# 1.net
KiCad netlist of a schematic drawn in EasyEDA Pro
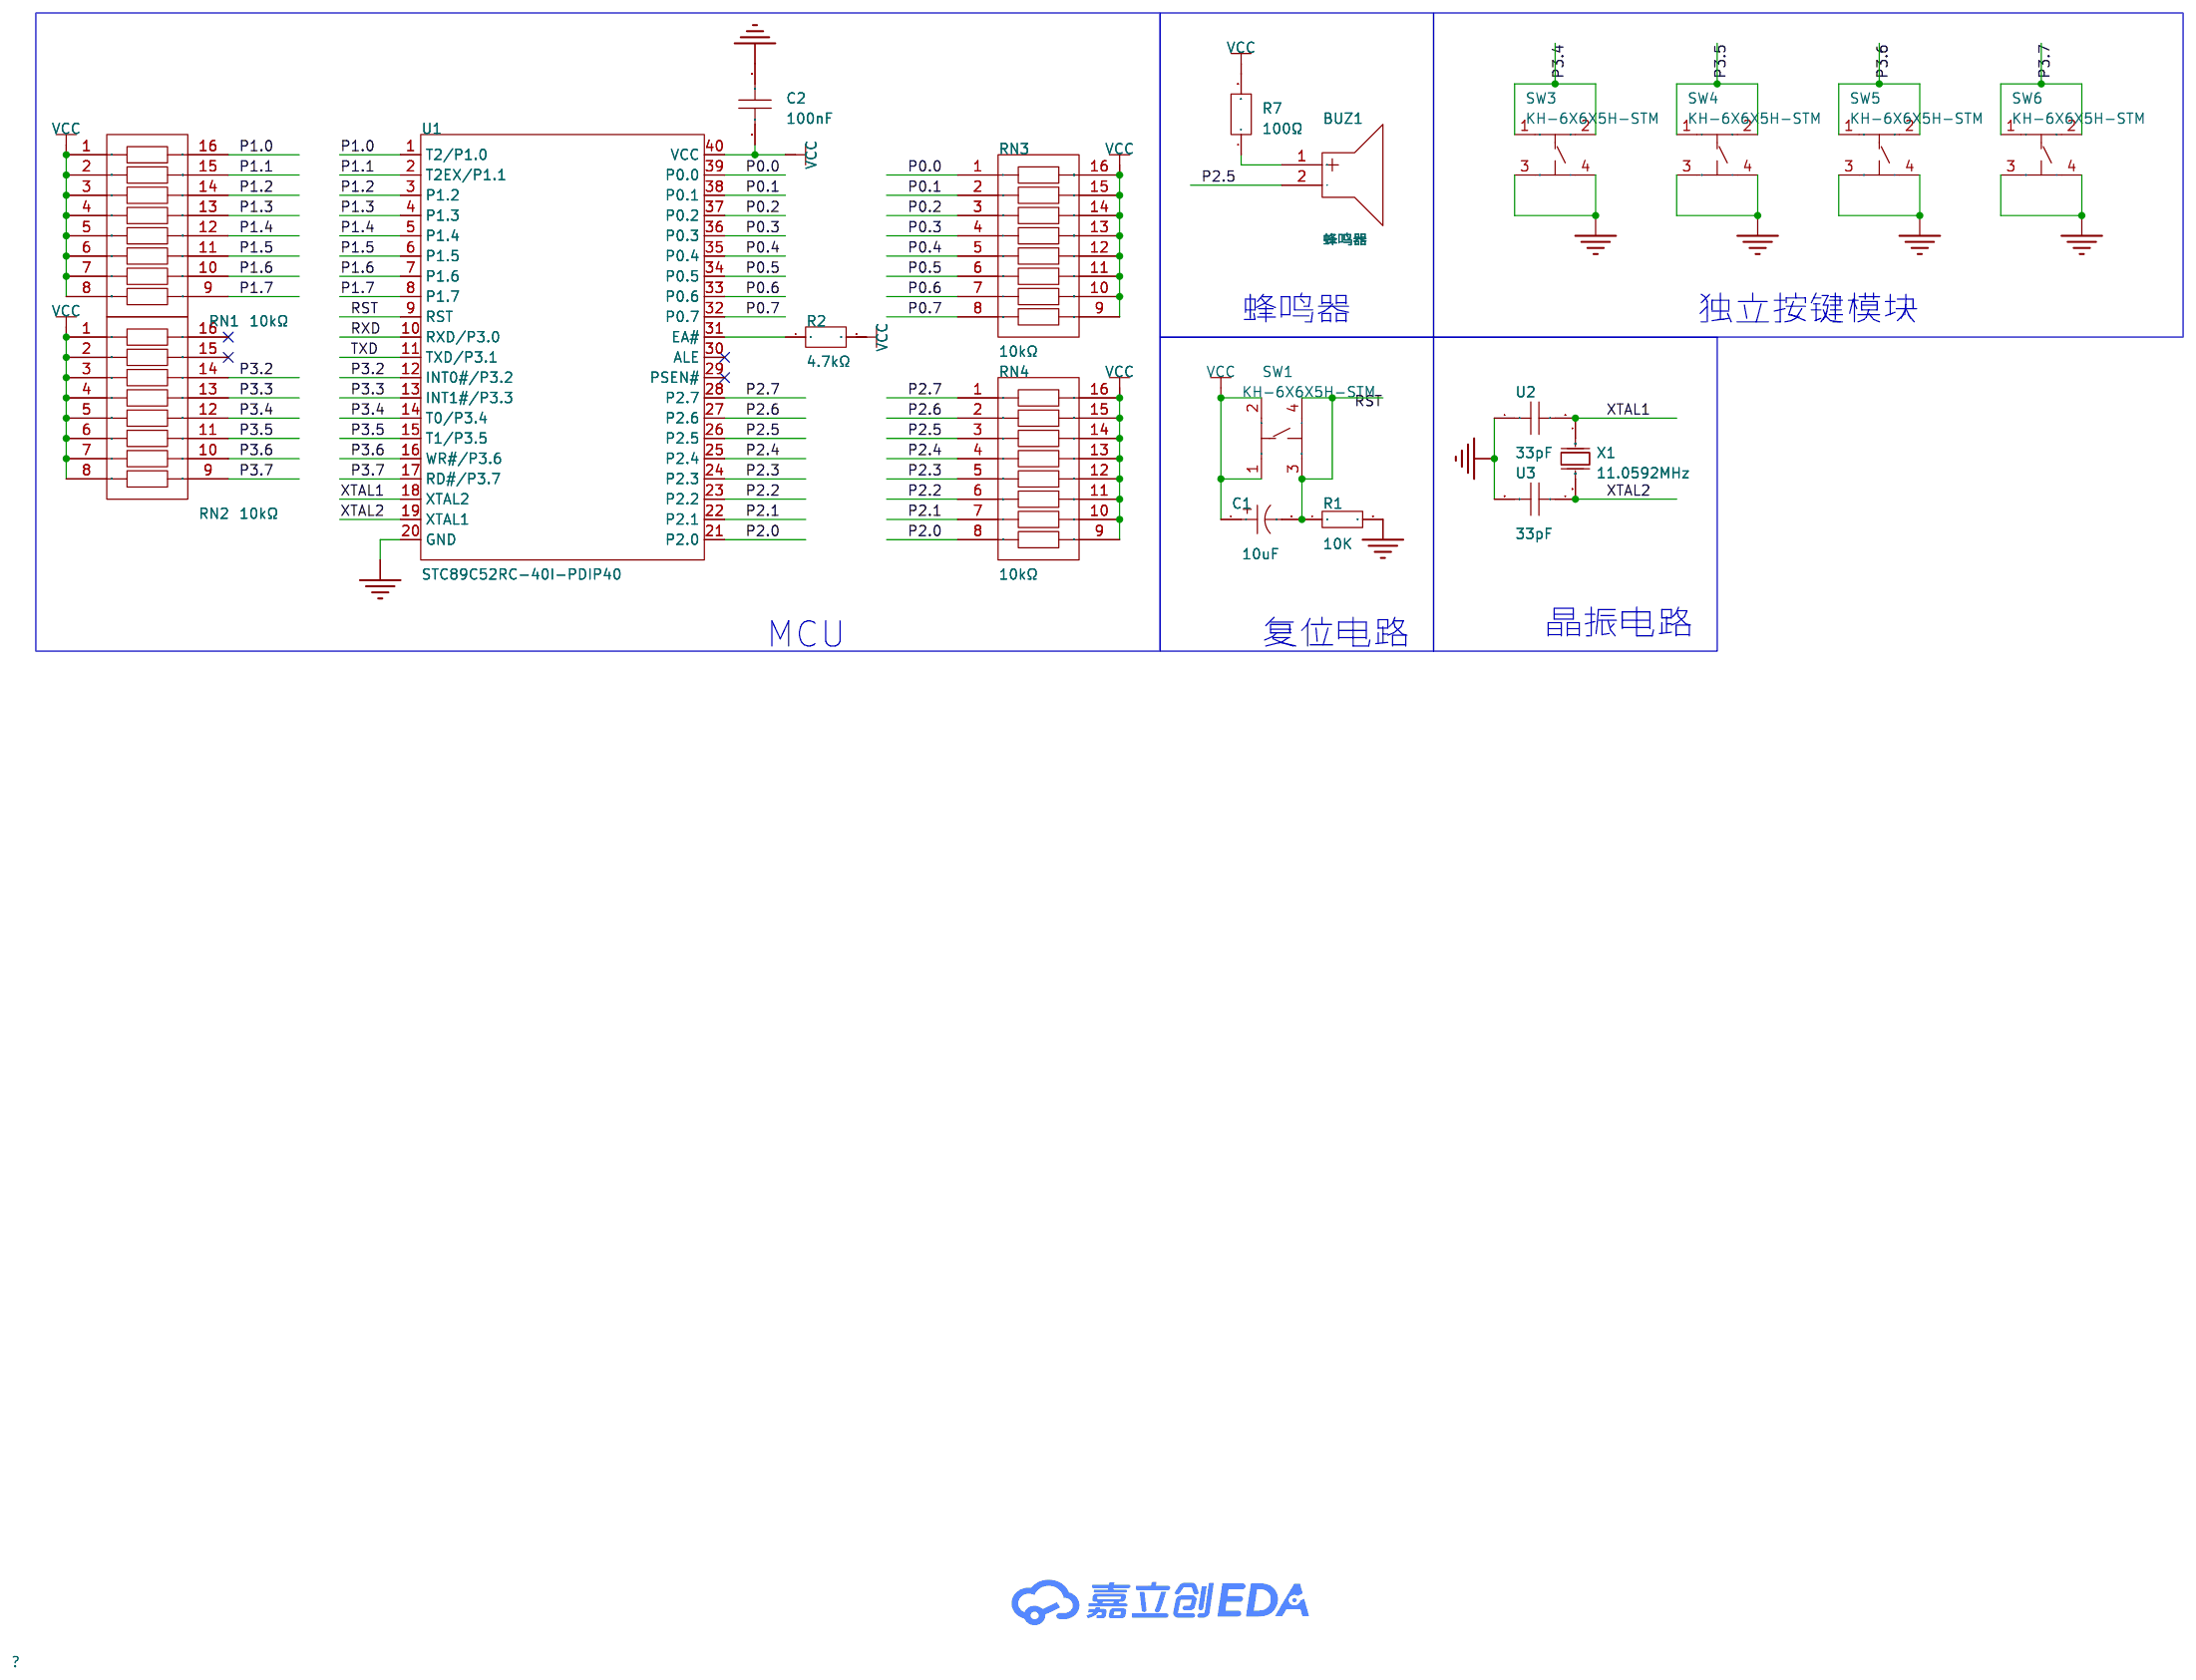
[diagram p0: schematic sheet]

(export (version "E")
  (design (tool "Eeschema 10.0.6"))
  (components
    (comp (ref "BUZ1")
      (value "蜂鸣器")
      (footprint "easyedapro:BUZ-TH_BD9.0-P5.00-D0.6-FD")
      (libsource (lib "easyedapro") (part "蜂鸣器"))
    )
    (comp (ref "C1")
      (value "10uF")
      (footprint "easyedapro:CAP-TH_BD10.0-P5.00-D0.6-FD_1")
      (description "容值:10uF;精度:±20%;额定电压:450V;纹波电流:200mA@100kHz;等效串联电阻(ESR):9Ω@100kHz;")
      (fields (field (name "Manufacturer Part") "CV100MPA16B") (field (name "Manufacturer") "TWBOR(伯鸿)"))
      (libsource (lib "easyedapro") (part "CV100MPA16B"))
    )
    (comp (ref "C2")
      (value "100nF")
      (footprint "easyedapro:C0603")
      (description "容值:100nF;精度:±10%;额定电压:25V;温度系数:X7R;")
      (fields
        (field (name "Manufacturer Part") "0603X7R104K250NT")
        (field (name "Manufacturer") "AIDE(爱迪电容)")
      )
      (libsource (lib "easyedapro") (part "0603X7R104K250NT"))
    )
    (comp (ref "R1") (value "10K") (footprint "easyedapro:R0603") (libsource (lib "easyedapro") (part "电阻")))
    (comp (ref "R2")
      (value "4.7kΩ")
      (footprint "easyedapro:R0805")
      (description "电阻类型:厚膜电阻;阻值:4.7kΩ;精度:±1%;功率:125mW;工作电压:-;温度系数:±100ppm/°C;")
      (fields
        (field (name "Manufacturer Part") "ERJ-U06F4701V")
        (field (name "Manufacturer") "PANASONIC(松下)")
      )
      (libsource (lib "easyedapro") (part "ERJ-U06F4701V"))
    )
    (comp (ref "R7")
      (value "100Ω")
      (footprint "easyedapro:R1206")
      (description "电阻类型:-;阻值:100Ω;精度:±5%;功率:250mW;工作电压:200V;")
      (fields
        (field (name "Manufacturer Part") "CQ06W4J0101T5E")
        (field (name "Manufacturer") "UNI-ROYAL(厚声)")
      )
      (libsource (lib "easyedapro") (part "CQ06W4J0101T5E"))
    )
    (comp (ref "RN1")
      (value "10kΩ")
      (footprint "easyedapro:DIP-16_L22.0-W6.7-P2.54-LS7.6-BL")
      (description "电阻器数:8;阻值:10kΩ;精度:±2%;单个元件功率:250mW;温度系数:±100ppm/°C;")
      (fields (field (name "Manufacturer Part") "4116R-1-103LF") (field (name "Manufacturer") "BOURNS"))
      (libsource (lib "easyedapro") (part "4116R-1-103LF"))
    )
    (comp (ref "RN2")
      (value "10kΩ")
      (footprint "easyedapro:DIP-16_L22.0-W6.7-P2.54-LS7.6-BL")
      (description "电阻器数:8;阻值:10kΩ;精度:±2%;单个元件功率:250mW;温度系数:±100ppm/°C;")
      (fields (field (name "Manufacturer Part") "4116R-1-103LF") (field (name "Manufacturer") "BOURNS"))
      (libsource (lib "easyedapro") (part "4116R-1-103LF"))
    )
    (comp (ref "RN3")
      (value "10kΩ")
      (footprint "easyedapro:DIP-16_L22.0-W6.7-P2.54-LS7.6-BL")
      (description "电阻器数:8;阻值:10kΩ;精度:±2%;单个元件功率:250mW;温度系数:±100ppm/°C;")
      (fields (field (name "Manufacturer Part") "4116R-1-103LF") (field (name "Manufacturer") "BOURNS"))
      (libsource (lib "easyedapro") (part "4116R-1-103LF"))
    )
    (comp (ref "RN4")
      (value "10kΩ")
      (footprint "easyedapro:DIP-16_L22.0-W6.7-P2.54-LS7.6-BL")
      (description "电阻器数:8;阻值:10kΩ;精度:±2%;单个元件功率:250mW;温度系数:±100ppm/°C;")
      (fields (field (name "Manufacturer Part") "4116R-1-103LF") (field (name "Manufacturer") "BOURNS"))
      (libsource (lib "easyedapro") (part "4116R-1-103LF"))
    )
    (comp (ref "SW1")
      (value "KH-6X6X5H-STM")
      (footprint "easyedapro:SW-SMD_4P-L6.0-W6.0-P4.50-LS9.0_H5.0")
      (description "电路结构:单刀单掷;按钮形状:圆形按钮;安装方式:立贴;开关长度:6mm;开关宽度:6mm;开关高度:5mm;带支架:不带;触点电流:50mA;额定电压(DC):12V;机械寿命:8万次;")
      (fields (field (name "Manufacturer") "kinghelm(金航标)"))
      (libsource (lib "easyedapro") (part "KH-6X6X5H-STM"))
    )
    (comp (ref "SW3")
      (value "KH-6X6X5H-STM")
      (footprint "easyedapro:SW-SMD_4P-L6.0-W6.0-P4.50-LS9.0_H5.0")
      (description "电路结构:单刀单掷;按钮形状:圆形按钮;安装方式:立贴;开关长度:6mm;开关宽度:6mm;开关高度:5mm;带支架:不带;触点电流:50mA;额定电压(DC):12V;机械寿命:8万次;")
      (fields (field (name "Manufacturer") "kinghelm(金航标)"))
      (libsource (lib "easyedapro") (part "KH-6X6X5H-STM"))
    )
    (comp (ref "SW4")
      (value "KH-6X6X5H-STM")
      (footprint "easyedapro:SW-SMD_4P-L6.0-W6.0-P4.50-LS9.0_H5.0")
      (description "电路结构:单刀单掷;按钮形状:圆形按钮;安装方式:立贴;开关长度:6mm;开关宽度:6mm;开关高度:5mm;带支架:不带;触点电流:50mA;额定电压(DC):12V;机械寿命:8万次;")
      (fields (field (name "Manufacturer") "kinghelm(金航标)"))
      (libsource (lib "easyedapro") (part "KH-6X6X5H-STM"))
    )
    (comp (ref "SW5")
      (value "KH-6X6X5H-STM")
      (footprint "easyedapro:SW-SMD_4P-L6.0-W6.0-P4.50-LS9.0_H5.0")
      (description "电路结构:单刀单掷;按钮形状:圆形按钮;安装方式:立贴;开关长度:6mm;开关宽度:6mm;开关高度:5mm;带支架:不带;触点电流:50mA;额定电压(DC):12V;机械寿命:8万次;")
      (fields (field (name "Manufacturer") "kinghelm(金航标)"))
      (libsource (lib "easyedapro") (part "KH-6X6X5H-STM"))
    )
    (comp (ref "SW6")
      (value "KH-6X6X5H-STM")
      (footprint "easyedapro:SW-SMD_4P-L6.0-W6.0-P4.50-LS9.0_H5.0")
      (description "电路结构:单刀单掷;按钮形状:圆形按钮;安装方式:立贴;开关长度:6mm;开关宽度:6mm;开关高度:5mm;带支架:不带;触点电流:50mA;额定电压(DC):12V;机械寿命:8万次;")
      (fields (field (name "Manufacturer") "kinghelm(金航标)"))
      (libsource (lib "easyedapro") (part "KH-6X6X5H-STM"))
    )
    (comp (ref "U1")
      (value "STC89C52RC-40I-PDIP40")
      (footprint "easyedapro:DIP-40_L52.0-W13.7-P2.54-LS15.2-BL")
      (description "CPU内核:51系列;应用领域:-;")
      (fields (field (name "Manufacturer") "STC"))
      (libsource (lib "easyedapro") (part "STC89C52RC-40I"))
    )
    (comp (ref "U2")
      (value "33pF")
      (footprint "easyedapro:C0603")
      (description "容值:33pF;精度:±1%;额定电压:50V;温度系数:-;")
      (fields
        (field (name "Manufacturer Part") "GRM1885C1H330FA01D")
        (field (name "Manufacturer") "muRata(村田)")
      )
      (libsource (lib "easyedapro") (part "GRM1885C1H330FA01D"))
    )
    (comp (ref "U3")
      (value "33pF")
      (footprint "easyedapro:C0603")
      (description "容值:33pF;精度:±1%;额定电压:50V;温度系数:-;")
      (fields
        (field (name "Manufacturer Part") "GRM1885C1H330FA01D")
        (field (name "Manufacturer") "muRata(村田)")
      )
      (libsource (lib "easyedapro") (part "GRM1885C1H330FA01D"))
    )
    (comp (ref "X1")
      (value "11.0592MHz")
      (footprint "easyedapro:HC-49US_L11.5-W4.5-P4.88")
      (description "晶振类型:直插晶振;频率:11.0592MHz;常温频差:±20ppm;负载电容:20pF;频率稳定度:±30ppm;")
      (fields
        (field (name "Manufacturer Part") "X49SD110592MSD2SC")
        (field (name "Manufacturer") "YXC(扬兴晶振)")
      )
      (libsource (lib "easyedapro") (part "X49SD110592MSD2SC"))
    )
  )
  (nets
    (net (code "1") (name "/P0.0") (class "Default")
      (node (ref "RN3") (pin "1") (pinfunction "1_1") (pintype "unspecified"))
      (node (ref "U1") (pin "39") (pinfunction "P0.0_39") (pintype "unspecified"))
    )
    (net (code "2") (name "/P0.1") (class "Default")
      (node (ref "RN3") (pin "2") (pinfunction "2_2") (pintype "unspecified"))
      (node (ref "U1") (pin "38") (pinfunction "P0.1_38") (pintype "unspecified"))
    )
    (net (code "3") (name "/P0.2") (class "Default")
      (node (ref "RN3") (pin "3") (pinfunction "3_3") (pintype "unspecified"))
      (node (ref "U1") (pin "37") (pinfunction "P0.2_37") (pintype "unspecified"))
    )
    (net (code "4") (name "/P0.3") (class "Default")
      (node (ref "RN3") (pin "4") (pinfunction "4_4") (pintype "unspecified"))
      (node (ref "U1") (pin "36") (pinfunction "P0.3_36") (pintype "unspecified"))
    )
    (net (code "5") (name "/P0.4") (class "Default")
      (node (ref "RN3") (pin "5") (pinfunction "5_5") (pintype "unspecified"))
      (node (ref "U1") (pin "35") (pinfunction "P0.4_35") (pintype "unspecified"))
    )
    (net (code "6") (name "/P0.5") (class "Default")
      (node (ref "RN3") (pin "6") (pinfunction "6_6") (pintype "unspecified"))
      (node (ref "U1") (pin "34") (pinfunction "P0.5_34") (pintype "unspecified"))
    )
    (net (code "7") (name "/P0.6") (class "Default")
      (node (ref "RN3") (pin "7") (pinfunction "7_7") (pintype "unspecified"))
      (node (ref "U1") (pin "33") (pinfunction "P0.6_33") (pintype "unspecified"))
    )
    (net (code "8") (name "/P0.7") (class "Default")
      (node (ref "RN3") (pin "8") (pinfunction "8_8") (pintype "unspecified"))
      (node (ref "U1") (pin "32") (pinfunction "P0.7_32") (pintype "unspecified"))
    )
    (net (code "9") (name "/P1.0") (class "Default")
      (node (ref "RN1") (pin "16") (pinfunction "16_16") (pintype "unspecified"))
      (node (ref "U1") (pin "1") (pinfunction "T2/P1.0_1") (pintype "unspecified"))
    )
    (net (code "10") (name "/P1.1") (class "Default")
      (node (ref "RN1") (pin "15") (pinfunction "15_15") (pintype "unspecified"))
      (node (ref "U1") (pin "2") (pinfunction "T2EX/P1.1_2") (pintype "unspecified"))
    )
    (net (code "11") (name "/P1.2") (class "Default")
      (node (ref "RN1") (pin "14") (pinfunction "14_14") (pintype "unspecified"))
      (node (ref "U1") (pin "3") (pinfunction "P1.2_3") (pintype "unspecified"))
    )
    (net (code "12") (name "/P1.3") (class "Default")
      (node (ref "RN1") (pin "13") (pinfunction "13_13") (pintype "unspecified"))
      (node (ref "U1") (pin "4") (pinfunction "P1.3_4") (pintype "unspecified"))
    )
    (net (code "13") (name "/P1.4") (class "Default")
      (node (ref "RN1") (pin "12") (pinfunction "12_12") (pintype "unspecified"))
      (node (ref "U1") (pin "5") (pinfunction "P1.4_5") (pintype "unspecified"))
    )
    (net (code "14") (name "/P1.5") (class "Default")
      (node (ref "RN1") (pin "11") (pinfunction "11_11") (pintype "unspecified"))
      (node (ref "U1") (pin "6") (pinfunction "P1.5_6") (pintype "unspecified"))
    )
    (net (code "15") (name "/P1.6") (class "Default")
      (node (ref "RN1") (pin "10") (pinfunction "10_10") (pintype "unspecified"))
      (node (ref "U1") (pin "7") (pinfunction "P1.6_7") (pintype "unspecified"))
    )
    (net (code "16") (name "/P1.7") (class "Default")
      (node (ref "RN1") (pin "9") (pinfunction "9_9") (pintype "unspecified"))
      (node (ref "U1") (pin "8") (pinfunction "P1.7_8") (pintype "unspecified"))
    )
    (net (code "17") (name "/P2.0") (class "Default")
      (node (ref "RN4") (pin "8") (pinfunction "8_8") (pintype "unspecified"))
      (node (ref "U1") (pin "21") (pinfunction "P2.0_21") (pintype "unspecified"))
    )
    (net (code "18") (name "/P2.1") (class "Default")
      (node (ref "RN4") (pin "7") (pinfunction "7_7") (pintype "unspecified"))
      (node (ref "U1") (pin "22") (pinfunction "P2.1_22") (pintype "unspecified"))
    )
    (net (code "19") (name "/P2.2") (class "Default")
      (node (ref "RN4") (pin "6") (pinfunction "6_6") (pintype "unspecified"))
      (node (ref "U1") (pin "23") (pinfunction "P2.2_23") (pintype "unspecified"))
    )
    (net (code "20") (name "/P2.3") (class "Default")
      (node (ref "RN4") (pin "5") (pinfunction "5_5") (pintype "unspecified"))
      (node (ref "U1") (pin "24") (pinfunction "P2.3_24") (pintype "unspecified"))
    )
    (net (code "21") (name "/P2.4") (class "Default")
      (node (ref "RN4") (pin "4") (pinfunction "4_4") (pintype "unspecified"))
      (node (ref "U1") (pin "25") (pinfunction "P2.4_25") (pintype "unspecified"))
    )
    (net (code "22") (name "/P2.5") (class "Default")
      (node (ref "BUZ1") (pin "2") (pinfunction "-_2") (pintype "unspecified"))
      (node (ref "RN4") (pin "3") (pinfunction "3_3") (pintype "unspecified"))
      (node (ref "U1") (pin "26") (pinfunction "P2.5_26") (pintype "unspecified"))
    )
    (net (code "23") (name "/P2.6") (class "Default")
      (node (ref "RN4") (pin "2") (pinfunction "2_2") (pintype "unspecified"))
      (node (ref "U1") (pin "27") (pinfunction "P2.6_27") (pintype "unspecified"))
    )
    (net (code "24") (name "/P2.7") (class "Default")
      (node (ref "RN4") (pin "1") (pinfunction "1_1") (pintype "unspecified"))
      (node (ref "U1") (pin "28") (pinfunction "P2.7_28") (pintype "unspecified"))
    )
    (net (code "25") (name "/P3.2") (class "Default")
      (node (ref "RN2") (pin "14") (pinfunction "14_14") (pintype "unspecified"))
      (node (ref "U1") (pin "12") (pinfunction "INT0#/P3.2_12") (pintype "unspecified"))
    )
    (net (code "26") (name "/P3.3") (class "Default")
      (node (ref "RN2") (pin "13") (pinfunction "13_13") (pintype "unspecified"))
      (node (ref "U1") (pin "13") (pinfunction "INT1#/P3.3_13") (pintype "unspecified"))
    )
    (net (code "27") (name "/P3.4") (class "Default")
      (node (ref "RN2") (pin "12") (pinfunction "12_12") (pintype "unspecified"))
      (node (ref "SW3") (pin "1") (pinfunction "1_1") (pintype "unspecified"))
      (node (ref "SW3") (pin "2") (pinfunction "2_2") (pintype "unspecified"))
      (node (ref "U1") (pin "14") (pinfunction "T0/P3.4_14") (pintype "unspecified"))
    )
    (net (code "28") (name "/P3.5") (class "Default")
      (node (ref "RN2") (pin "11") (pinfunction "11_11") (pintype "unspecified"))
      (node (ref "SW4") (pin "1") (pinfunction "1_1") (pintype "unspecified"))
      (node (ref "SW4") (pin "2") (pinfunction "2_2") (pintype "unspecified"))
      (node (ref "U1") (pin "15") (pinfunction "T1/P3.5_15") (pintype "unspecified"))
    )
    (net (code "29") (name "/P3.6") (class "Default")
      (node (ref "RN2") (pin "10") (pinfunction "10_10") (pintype "unspecified"))
      (node (ref "SW5") (pin "1") (pinfunction "1_1") (pintype "unspecified"))
      (node (ref "SW5") (pin "2") (pinfunction "2_2") (pintype "unspecified"))
      (node (ref "U1") (pin "16") (pinfunction "WR#/P3.6_16") (pintype "unspecified"))
    )
    (net (code "30") (name "/P3.7") (class "Default")
      (node (ref "RN2") (pin "9") (pinfunction "9_9") (pintype "unspecified"))
      (node (ref "SW6") (pin "1") (pinfunction "1_1") (pintype "unspecified"))
      (node (ref "SW6") (pin "2") (pinfunction "2_2") (pintype "unspecified"))
      (node (ref "U1") (pin "17") (pinfunction "RD#/P3.7_17") (pintype "unspecified"))
    )
    (net (code "31") (name "/RST") (class "Default")
      (node (ref "C1") (pin "2") (pinfunction "2_2") (pintype "input"))
      (node (ref "R1") (pin "1") (pinfunction "1_1") (pintype "input"))
      (node (ref "SW1") (pin "3") (pinfunction "3_3") (pintype "unspecified"))
      (node (ref "SW1") (pin "4") (pinfunction "4_4") (pintype "unspecified"))
      (node (ref "U1") (pin "9") (pinfunction "RST_9") (pintype "unspecified"))
    )
    (net (code "32") (name "/RXD") (class "Default")
      (node (ref "U1") (pin "10") (pinfunction "RXD/P3.0_10") (pintype "unspecified"))
    )
    (net (code "33") (name "/TXD") (class "Default")
      (node (ref "U1") (pin "11") (pinfunction "TXD/P3.1_11") (pintype "unspecified"))
    )
    (net (code "34") (name "/XTAL1") (class "Default")
      (node (ref "U1") (pin "18") (pinfunction "XTAL2_18") (pintype "unspecified"))
      (node (ref "U2") (pin "2") (pinfunction "2_2") (pintype "unspecified"))
      (node (ref "X1") (pin "1") (pinfunction "OSC1_1") (pintype "input"))
    )
    (net (code "35") (name "/XTAL2") (class "Default")
      (node (ref "U1") (pin "19") (pinfunction "XTAL1_19") (pintype "unspecified"))
      (node (ref "U3") (pin "1") (pinfunction "1_1") (pintype "unspecified"))
      (node (ref "X1") (pin "2") (pinfunction "OSC2_2") (pintype "input"))
    )
    (net (code "36") (name "GND") (class "Default")
      (node (ref "C2") (pin "2") (pinfunction "2_2") (pintype "unspecified"))
      (node (ref "R1") (pin "2") (pinfunction "2_2") (pintype "input"))
      (node (ref "SW3") (pin "3") (pinfunction "3_3") (pintype "unspecified"))
      (node (ref "SW3") (pin "4") (pinfunction "4_4") (pintype "unspecified"))
      (node (ref "SW4") (pin "3") (pinfunction "3_3") (pintype "unspecified"))
      (node (ref "SW4") (pin "4") (pinfunction "4_4") (pintype "unspecified"))
      (node (ref "SW5") (pin "3") (pinfunction "3_3") (pintype "unspecified"))
      (node (ref "SW5") (pin "4") (pinfunction "4_4") (pintype "unspecified"))
      (node (ref "SW6") (pin "3") (pinfunction "3_3") (pintype "unspecified"))
      (node (ref "SW6") (pin "4") (pinfunction "4_4") (pintype "unspecified"))
      (node (ref "U1") (pin "20") (pinfunction "GND_20") (pintype "unspecified"))
      (node (ref "U2") (pin "1") (pinfunction "1_1") (pintype "unspecified"))
      (node (ref "U3") (pin "2") (pinfunction "2_2") (pintype "unspecified"))
    )
    (net (code "37") (name "Net-(BUZ1-+)") (class "Default")
      (node (ref "BUZ1") (pin "1") (pinfunction "+_1") (pintype "unspecified"))
      (node (ref "R7") (pin "1") (pinfunction "1_1") (pintype "unspecified"))
    )
    (net (code "38") (name "Net-(U1-EA#)") (class "Default")
      (node (ref "R2") (pin "1") (pinfunction "1_1") (pintype "unspecified"))
      (node (ref "U1") (pin "31") (pinfunction "EA#_31") (pintype "unspecified"))
    )
    (net (code "39") (name "VCC") (class "Default")
      (node (ref "C1") (pin "1") (pinfunction "1_1") (pintype "input"))
      (node (ref "C2") (pin "1") (pinfunction "1_1") (pintype "unspecified"))
      (node (ref "R2") (pin "2") (pinfunction "2_2") (pintype "unspecified"))
      (node (ref "R7") (pin "2") (pinfunction "2_2") (pintype "unspecified"))
      (node (ref "RN1") (pin "1") (pinfunction "1_1") (pintype "unspecified"))
      (node (ref "RN1") (pin "2") (pinfunction "2_2") (pintype "unspecified"))
      (node (ref "RN1") (pin "3") (pinfunction "3_3") (pintype "unspecified"))
      (node (ref "RN1") (pin "4") (pinfunction "4_4") (pintype "unspecified"))
      (node (ref "RN1") (pin "5") (pinfunction "5_5") (pintype "unspecified"))
      (node (ref "RN1") (pin "6") (pinfunction "6_6") (pintype "unspecified"))
      (node (ref "RN1") (pin "7") (pinfunction "7_7") (pintype "unspecified"))
      (node (ref "RN1") (pin "8") (pinfunction "8_8") (pintype "unspecified"))
      (node (ref "RN2") (pin "1") (pinfunction "1_1") (pintype "unspecified"))
      (node (ref "RN2") (pin "2") (pinfunction "2_2") (pintype "unspecified"))
      (node (ref "RN2") (pin "3") (pinfunction "3_3") (pintype "unspecified"))
      (node (ref "RN2") (pin "4") (pinfunction "4_4") (pintype "unspecified"))
      (node (ref "RN2") (pin "5") (pinfunction "5_5") (pintype "unspecified"))
      (node (ref "RN2") (pin "6") (pinfunction "6_6") (pintype "unspecified"))
      (node (ref "RN2") (pin "7") (pinfunction "7_7") (pintype "unspecified"))
      (node (ref "RN2") (pin "8") (pinfunction "8_8") (pintype "unspecified"))
      (node (ref "RN3") (pin "10") (pinfunction "10_10") (pintype "unspecified"))
      (node (ref "RN3") (pin "11") (pinfunction "11_11") (pintype "unspecified"))
      (node (ref "RN3") (pin "12") (pinfunction "12_12") (pintype "unspecified"))
      (node (ref "RN3") (pin "13") (pinfunction "13_13") (pintype "unspecified"))
      (node (ref "RN3") (pin "14") (pinfunction "14_14") (pintype "unspecified"))
      (node (ref "RN3") (pin "15") (pinfunction "15_15") (pintype "unspecified"))
      (node (ref "RN3") (pin "16") (pinfunction "16_16") (pintype "unspecified"))
      (node (ref "RN3") (pin "9") (pinfunction "9_9") (pintype "unspecified"))
      (node (ref "RN4") (pin "10") (pinfunction "10_10") (pintype "unspecified"))
      (node (ref "RN4") (pin "11") (pinfunction "11_11") (pintype "unspecified"))
      (node (ref "RN4") (pin "12") (pinfunction "12_12") (pintype "unspecified"))
      (node (ref "RN4") (pin "13") (pinfunction "13_13") (pintype "unspecified"))
      (node (ref "RN4") (pin "14") (pinfunction "14_14") (pintype "unspecified"))
      (node (ref "RN4") (pin "15") (pinfunction "15_15") (pintype "unspecified"))
      (node (ref "RN4") (pin "16") (pinfunction "16_16") (pintype "unspecified"))
      (node (ref "RN4") (pin "9") (pinfunction "9_9") (pintype "unspecified"))
      (node (ref "SW1") (pin "1") (pinfunction "1_1") (pintype "unspecified"))
      (node (ref "SW1") (pin "2") (pinfunction "2_2") (pintype "unspecified"))
      (node (ref "U1") (pin "40") (pinfunction "VCC_40") (pintype "unspecified"))
    )
    (net (code "40") (name "unconnected-(RN2-Pad15)") (class "Default")
      (node (ref "RN2") (pin "15") (pinfunction "15_15") (pintype "unspecified+no_connect"))
    )
    (net (code "41") (name "unconnected-(RN2-Pad16)") (class "Default")
      (node (ref "RN2") (pin "16") (pinfunction "16_16") (pintype "unspecified+no_connect"))
    )
    (net (code "42") (name "unconnected-(U1-ALE-Pad30)") (class "Default")
      (node (ref "U1") (pin "30") (pinfunction "ALE_30") (pintype "unspecified+no_connect"))
    )
    (net (code "43") (name "unconnected-(U1-PSEN#-Pad29)") (class "Default")
      (node (ref "U1") (pin "29") (pinfunction "PSEN#_29") (pintype "unspecified+no_connect"))
    )
  )
)
